# Sheet3.net
KiCad netlist of a schematic drawn in Altium Designer
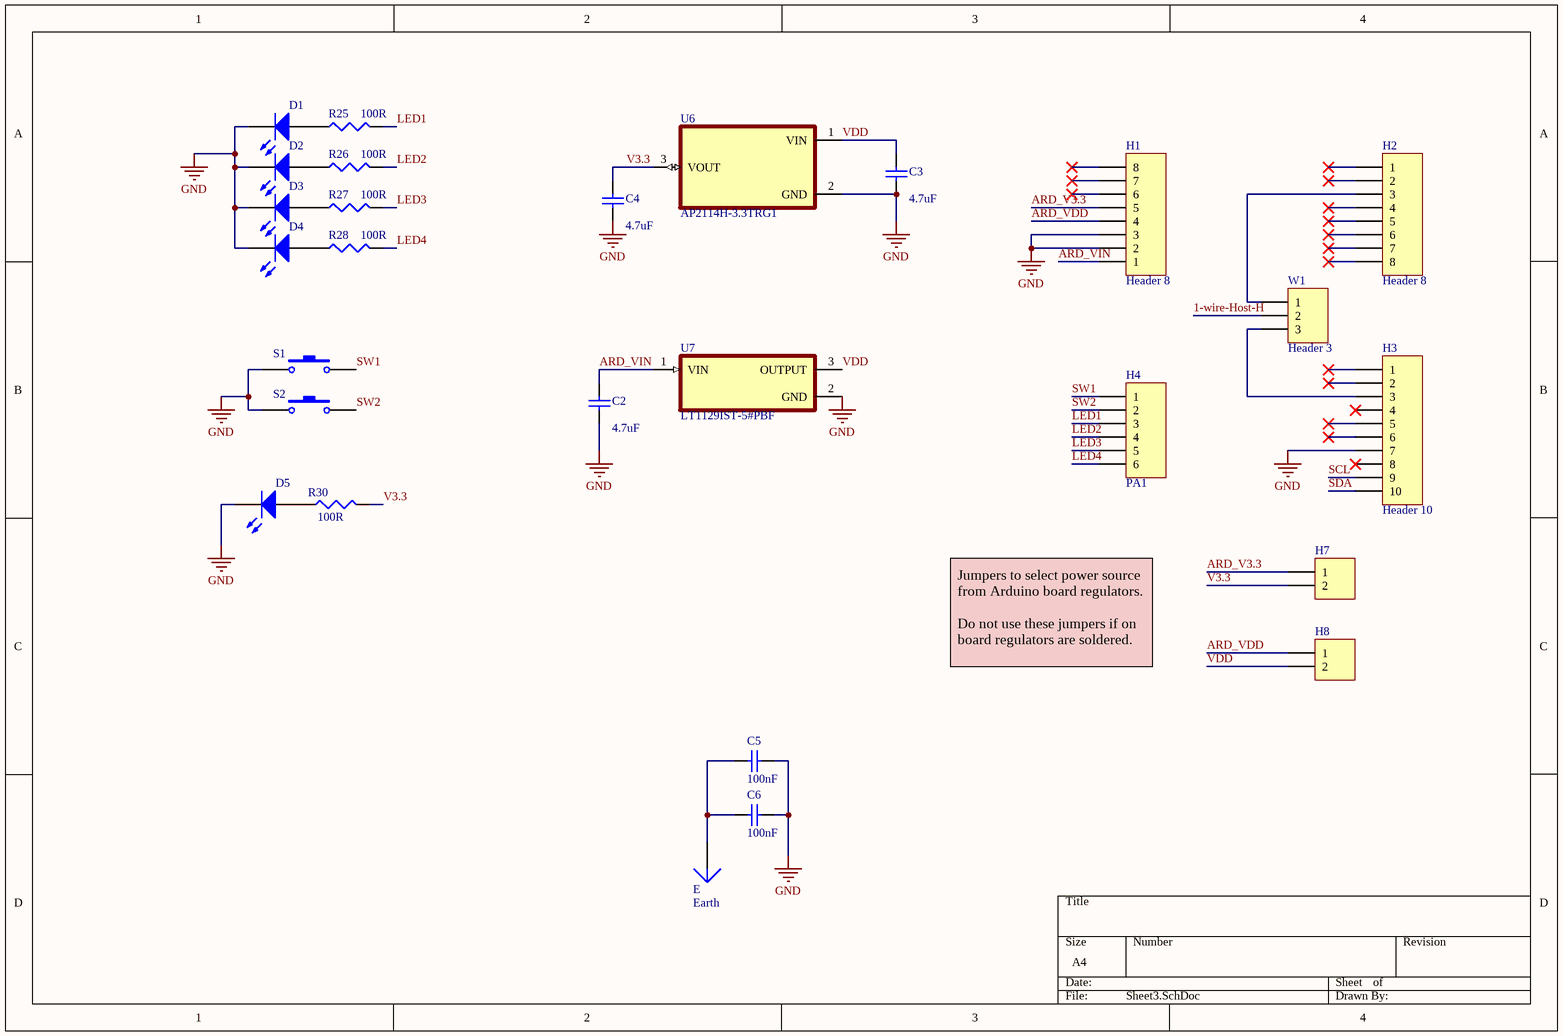
[diagram p0: Sheet3.SchDoc]

(export (version "E")
  (design (tool "Eeschema 10.0.6"))
  (components
    (comp (ref "C2")
      (value "4.7uF")
      (footprint "C0805")
      (description "Capacitor (Semiconductor SIM Model)")
      (fields (field (name "PUBLISHER") "Altium Limited"))
      (libsource (lib "Miscellaneous Devices") (part "Cap Semi"))
    )
    (comp (ref "C3")
      (value "4.7uF")
      (footprint "C0805")
      (description "Capacitor (Semiconductor SIM Model)")
      (fields (field (name "PUBLISHER") "Altium Limited"))
      (libsource (lib "Miscellaneous Devices") (part "Cap Semi"))
    )
    (comp (ref "C4")
      (value "4.7uF")
      (footprint "C0805")
      (description "Capacitor (Semiconductor SIM Model)")
      (fields (field (name "PUBLISHER") "Altium Limited"))
      (libsource (lib "Miscellaneous Devices") (part "Cap Semi"))
    )
    (comp (ref "C5")
      (value "100nF")
      (footprint "CAPC1608L")
      (description "Capacitor (Semiconductor SIM Model)")
      (fields (field (name "PUBLISHER") "Altium Limited"))
      (libsource (lib "Miscellaneous Devices") (part "Cap Semi"))
    )
    (comp (ref "C6")
      (value "100nF")
      (footprint "CAPC1608L")
      (description "Capacitor (Semiconductor SIM Model)")
      (fields (field (name "PUBLISHER") "Altium Limited"))
      (libsource (lib "Miscellaneous Devices") (part "Cap Semi"))
    )
    (comp (ref "D1")
      (value "~")
      (footprint "6-0805_N")
      (description "Typical BLUE SiC LED")
      (fields (field (name "PUBLISHER") "Altium Limited"))
      (libsource (lib "Miscellaneous Devices") (part "LED3"))
    )
    (comp (ref "D2")
      (value "~")
      (footprint "6-0805_N")
      (description "Typical BLUE SiC LED")
      (fields (field (name "PUBLISHER") "Altium Limited"))
      (libsource (lib "Miscellaneous Devices") (part "LED3"))
    )
    (comp (ref "D3")
      (value "~")
      (footprint "6-0805_N")
      (description "Typical BLUE SiC LED")
      (fields (field (name "PUBLISHER") "Altium Limited"))
      (libsource (lib "Miscellaneous Devices") (part "LED3"))
    )
    (comp (ref "D4")
      (value "~")
      (footprint "6-0805_N")
      (description "Typical BLUE SiC LED")
      (fields (field (name "PUBLISHER") "Altium Limited"))
      (libsource (lib "Miscellaneous Devices") (part "LED3"))
    )
    (comp (ref "D5")
      (value "~")
      (footprint "6-0805_N")
      (description "Typical BLUE SiC LED")
      (fields (field (name "PUBLISHER") "Altium Limited"))
      (libsource (lib "Miscellaneous Devices") (part "LED3"))
    )
    (comp (ref "E")
      (value "Earth")
      (footprint "PIN1")
      (description "Plug")
      (fields (field (name "PUBLISHER") "Altium Limited"))
      (libsource (lib "Miscellaneous Connectors") (part "Plug"))
    )
    (comp (ref "H1")
      (value "Header 8")
      (footprint "HDR1X8")
      (description "Header, 8-Pin")
      (fields (field (name "PUBLISHER") "Altium Limited"))
      (libsource (lib "") (part "Header 8_1"))
    )
    (comp (ref "H2")
      (value "Header 8")
      (footprint "HDR1X8")
      (description "Header, 8-Pin")
      (fields (field (name "PUBLISHER") "Altium Limited"))
      (libsource (lib "Miscellaneous Connectors") (part "Header 8"))
    )
    (comp (ref "H3")
      (value "Header 10")
      (footprint "HDR1X10")
      (description "Header, 10-Pin")
      (fields (field (name "PUBLISHER") "Altium Limited"))
      (libsource (lib "Miscellaneous Connectors") (part "Header 10"))
    )
    (comp (ref "H4")
      (value "PA1")
      (footprint "HDR1X6")
      (description "Header, 6-Pin")
      (fields (field (name "PUBLISHER") "Altium Limited"))
      (libsource (lib "Miscellaneous Connectors") (part "Header 6"))
    )
    (comp (ref "H7")
      (value "~")
      (footprint "HDR1X2")
      (description "Header, 2-Pin")
      (fields (field (name "PUBLISHER") "Altium Limited"))
      (libsource (lib "Miscellaneous Connectors") (part "Header 2"))
    )
    (comp (ref "H8")
      (value "~")
      (footprint "HDR1X2")
      (description "Header, 2-Pin")
      (fields (field (name "PUBLISHER") "Altium Limited"))
      (libsource (lib "Miscellaneous Connectors") (part "Header 2"))
    )
    (comp (ref "R25")
      (value "100R")
      (footprint "J1-0603")
      (description "Resistor")
      (fields (field (name "PUBLISHER") "Altium Limited"))
      (libsource (lib "Miscellaneous Devices") (part "Res3"))
    )
    (comp (ref "R26")
      (value "100R")
      (footprint "J1-0603")
      (description "Resistor")
      (fields (field (name "PUBLISHER") "Altium Limited"))
      (libsource (lib "Miscellaneous Devices") (part "Res3"))
    )
    (comp (ref "R27")
      (value "100R")
      (footprint "J1-0603")
      (description "Resistor")
      (fields (field (name "PUBLISHER") "Altium Limited"))
      (libsource (lib "Miscellaneous Devices") (part "Res3"))
    )
    (comp (ref "R28")
      (value "100R")
      (footprint "J1-0603")
      (description "Resistor")
      (fields (field (name "PUBLISHER") "Altium Limited"))
      (libsource (lib "Miscellaneous Devices") (part "Res3"))
    )
    (comp (ref "R30")
      (value "100R")
      (footprint "J1-0603")
      (description "Resistor")
      (fields (field (name "PUBLISHER") "Altium Limited"))
      (libsource (lib "Miscellaneous Devices") (part "Res3"))
    )
    (comp (ref "S1")
      (value "~")
      (footprint "PTS525SM08SMTR2LFS")
      (description "Switch")
      (fields (field (name "PUBLISHER") "Altium Limited"))
      (libsource (lib "Miscellaneous Devices") (part "SW-PB"))
    )
    (comp (ref "S2")
      (value "~")
      (footprint "PTS525SM08SMTR2LFS")
      (description "Switch")
      (fields (field (name "PUBLISHER") "Altium Limited"))
      (libsource (lib "Miscellaneous Devices") (part "SW-PB"))
    )
    (comp (ref "U6")
      (value "AP2114H-3.3TRG1")
      (footprint "AP2114H-3.3TRG1:SOT230P700X180-4N")
      (fields (field (name "MF") "{'manufacturer': u'Diodes Inc.'}"))
      (libsource (lib "*") (part "AP2114H-3.3TRG1"))
    )
    (comp (ref "U7")
      (value "LT1129IST-5#PBF")
      (footprint "LT1129IST-5#PBF:SOT230P700X180-4N")
      (fields (field (name "MF") "{'manufacturer': u'Analog Devices'}"))
      (libsource (lib "LT1129IST-5#PBF") (part "LT1129IST-5#PBF"))
    )
    (comp (ref "W1")
      (value "Header 3")
      (footprint "HDR1X3")
      (description "Header, 3-Pin")
      (fields (field (name "PUBLISHER") "Altium Limited"))
      (libsource (lib "Miscellaneous Connectors") (part "Header 3"))
    )
  )
  (nets
    (net (code "1") (name "/1-wire-Host-H") (class "Default")
      (node (ref "W1") (pin "2") (pinfunction "2_2") (pintype "passive"))
    )
    (net (code "2") (name "/ARD_V3.3") (class "Default")
      (node (ref "H1") (pin "5") (pinfunction "5_5") (pintype "passive"))
      (node (ref "H7") (pin "1") (pinfunction "1_1") (pintype "passive"))
    )
    (net (code "3") (name "/ARD_VDD") (class "Default")
      (node (ref "H1") (pin "4") (pinfunction "4_4") (pintype "passive"))
      (node (ref "H8") (pin "1") (pinfunction "1_1") (pintype "passive"))
    )
    (net (code "4") (name "/ARD_VIN") (class "Default")
      (node (ref "C2") (pin "2") (pinfunction "2_2") (pintype "passive"))
      (node (ref "H1") (pin "1") (pinfunction "1_1") (pintype "passive"))
      (node (ref "U7") (pin "1") (pinfunction "VIN_1") (pintype "input"))
    )
    (net (code "5") (name "/LED1") (class "Default")
      (node (ref "H4") (pin "3") (pinfunction "3_3") (pintype "passive"))
      (node (ref "R25") (pin "1") (pinfunction "1_1") (pintype "passive"))
    )
    (net (code "6") (name "/LED2") (class "Default")
      (node (ref "H4") (pin "4") (pinfunction "4_4") (pintype "passive"))
      (node (ref "R26") (pin "1") (pinfunction "1_1") (pintype "passive"))
    )
    (net (code "7") (name "/LED3") (class "Default")
      (node (ref "H4") (pin "5") (pinfunction "5_5") (pintype "passive"))
      (node (ref "R27") (pin "1") (pinfunction "1_1") (pintype "passive"))
    )
    (net (code "8") (name "/LED4") (class "Default")
      (node (ref "H4") (pin "6") (pinfunction "6_6") (pintype "passive"))
      (node (ref "R28") (pin "1") (pinfunction "1_1") (pintype "passive"))
    )
    (net (code "9") (name "/SCL") (class "Default")
      (node (ref "H3") (pin "9") (pinfunction "9_9") (pintype "passive"))
    )
    (net (code "10") (name "/SDA") (class "Default")
      (node (ref "H3") (pin "10") (pinfunction "10_10") (pintype "passive"))
    )
    (net (code "11") (name "/SW1") (class "Default")
      (node (ref "H4") (pin "1") (pinfunction "1_1") (pintype "passive"))
      (node (ref "S1") (pin "2") (pinfunction "2_2") (pintype "passive"))
    )
    (net (code "12") (name "/SW2") (class "Default")
      (node (ref "H4") (pin "2") (pinfunction "2_2") (pintype "passive"))
      (node (ref "S2") (pin "2") (pinfunction "2_2") (pintype "passive"))
    )
    (net (code "13") (name "/V3.3") (class "Default")
      (node (ref "C4") (pin "2") (pinfunction "2_2") (pintype "passive"))
      (node (ref "H7") (pin "2") (pinfunction "2_2") (pintype "passive"))
      (node (ref "R30") (pin "1") (pinfunction "1_1") (pintype "passive"))
      (node (ref "U6") (pin "3") (pinfunction "VOUT_3") (pintype "bidirectional"))
    )
    (net (code "14") (name "/VDD") (class "Default")
      (node (ref "C3") (pin "2") (pinfunction "2_2") (pintype "passive"))
      (node (ref "H8") (pin "2") (pinfunction "2_2") (pintype "passive"))
      (node (ref "U6") (pin "1") (pinfunction "VIN_1") (pintype "power_in"))
      (node (ref "U7") (pin "3") (pinfunction "OUTPUT_3") (pintype "power_in"))
    )
    (net (code "15") (name "GND") (class "Default")
      (node (ref "C2") (pin "1") (pinfunction "1_1") (pintype "passive"))
      (node (ref "C3") (pin "1") (pinfunction "1_1") (pintype "passive"))
      (node (ref "C4") (pin "1") (pinfunction "1_1") (pintype "passive"))
      (node (ref "C5") (pin "2") (pinfunction "2_2") (pintype "passive"))
      (node (ref "C6") (pin "2") (pinfunction "2_2") (pintype "passive"))
      (node (ref "D1") (pin "2") (pinfunction "K_2") (pintype "passive"))
      (node (ref "D2") (pin "2") (pinfunction "K_2") (pintype "passive"))
      (node (ref "D3") (pin "2") (pinfunction "K_2") (pintype "passive"))
      (node (ref "D4") (pin "2") (pinfunction "K_2") (pintype "passive"))
      (node (ref "D5") (pin "2") (pinfunction "K_2") (pintype "passive"))
      (node (ref "H1") (pin "2") (pinfunction "2_2") (pintype "passive"))
      (node (ref "H1") (pin "3") (pinfunction "3_3") (pintype "passive"))
      (node (ref "H3") (pin "7") (pinfunction "7_7") (pintype "passive"))
      (node (ref "S1") (pin "1") (pinfunction "1_1") (pintype "passive"))
      (node (ref "S2") (pin "1") (pinfunction "1_1") (pintype "passive"))
      (node (ref "U6") (pin "2") (pinfunction "GND_2") (pintype "power_in"))
      (node (ref "U7") (pin "2") (pinfunction "GND_2") (pintype "power_in"))
    )
    (net (code "16") (name "Net-(C5-Pad1)") (class "Default")
      (node (ref "C5") (pin "1") (pinfunction "1_1") (pintype "passive"))
      (node (ref "C6") (pin "1") (pinfunction "1_1") (pintype "passive"))
      (node (ref "E") (pin "1") (pinfunction "1_1") (pintype "passive"))
    )
    (net (code "17") (name "Net-(D1-A)") (class "Default")
      (node (ref "D1") (pin "1") (pinfunction "A_1") (pintype "passive"))
      (node (ref "R25") (pin "2") (pinfunction "2_2") (pintype "passive"))
    )
    (net (code "18") (name "Net-(D2-A)") (class "Default")
      (node (ref "D2") (pin "1") (pinfunction "A_1") (pintype "passive"))
      (node (ref "R26") (pin "2") (pinfunction "2_2") (pintype "passive"))
    )
    (net (code "19") (name "Net-(D3-A)") (class "Default")
      (node (ref "D3") (pin "1") (pinfunction "A_1") (pintype "passive"))
      (node (ref "R27") (pin "2") (pinfunction "2_2") (pintype "passive"))
    )
    (net (code "20") (name "Net-(D4-A)") (class "Default")
      (node (ref "D4") (pin "1") (pinfunction "A_1") (pintype "passive"))
      (node (ref "R28") (pin "2") (pinfunction "2_2") (pintype "passive"))
    )
    (net (code "21") (name "Net-(D5-A)") (class "Default")
      (node (ref "D5") (pin "1") (pinfunction "A_1") (pintype "passive"))
      (node (ref "R30") (pin "2") (pinfunction "2_2") (pintype "passive"))
    )
    (net (code "22") (name "Net-(H2-Pad3)") (class "Default")
      (node (ref "H2") (pin "3") (pinfunction "3_3") (pintype "passive"))
      (node (ref "W1") (pin "1") (pinfunction "1_1") (pintype "passive"))
    )
    (net (code "23") (name "Net-(H3-Pad3)") (class "Default")
      (node (ref "H3") (pin "3") (pinfunction "3_3") (pintype "passive"))
      (node (ref "W1") (pin "3") (pinfunction "3_3") (pintype "passive"))
    )
    (net (code "24") (name "unconnected-(H1-Pad6)") (class "Default")
      (node (ref "H1") (pin "6") (pinfunction "6_6") (pintype "passive+no_connect"))
    )
    (net (code "25") (name "unconnected-(H1-Pad7)") (class "Default")
      (node (ref "H1") (pin "7") (pinfunction "7_7") (pintype "passive+no_connect"))
    )
    (net (code "26") (name "unconnected-(H1-Pad8)") (class "Default")
      (node (ref "H1") (pin "8") (pinfunction "8_8") (pintype "passive+no_connect"))
    )
    (net (code "27") (name "unconnected-(H2-Pad1)") (class "Default")
      (node (ref "H2") (pin "1") (pinfunction "1_1") (pintype "passive+no_connect"))
    )
    (net (code "28") (name "unconnected-(H2-Pad2)") (class "Default")
      (node (ref "H2") (pin "2") (pinfunction "2_2") (pintype "passive+no_connect"))
    )
    (net (code "29") (name "unconnected-(H2-Pad4)") (class "Default")
      (node (ref "H2") (pin "4") (pinfunction "4_4") (pintype "passive+no_connect"))
    )
    (net (code "30") (name "unconnected-(H2-Pad5)") (class "Default")
      (node (ref "H2") (pin "5") (pinfunction "5_5") (pintype "passive+no_connect"))
    )
    (net (code "31") (name "unconnected-(H2-Pad6)") (class "Default")
      (node (ref "H2") (pin "6") (pinfunction "6_6") (pintype "passive+no_connect"))
    )
    (net (code "32") (name "unconnected-(H2-Pad7)") (class "Default")
      (node (ref "H2") (pin "7") (pinfunction "7_7") (pintype "passive+no_connect"))
    )
    (net (code "33") (name "unconnected-(H2-Pad8)") (class "Default")
      (node (ref "H2") (pin "8") (pinfunction "8_8") (pintype "passive+no_connect"))
    )
    (net (code "34") (name "unconnected-(H3-Pad1)") (class "Default")
      (node (ref "H3") (pin "1") (pinfunction "1_1") (pintype "passive+no_connect"))
    )
    (net (code "35") (name "unconnected-(H3-Pad2)") (class "Default")
      (node (ref "H3") (pin "2") (pinfunction "2_2") (pintype "passive+no_connect"))
    )
    (net (code "36") (name "unconnected-(H3-Pad4)") (class "Default")
      (node (ref "H3") (pin "4") (pinfunction "4_4") (pintype "passive+no_connect"))
    )
    (net (code "37") (name "unconnected-(H3-Pad5)") (class "Default")
      (node (ref "H3") (pin "5") (pinfunction "5_5") (pintype "passive+no_connect"))
    )
    (net (code "38") (name "unconnected-(H3-Pad6)") (class "Default")
      (node (ref "H3") (pin "6") (pinfunction "6_6") (pintype "passive+no_connect"))
    )
    (net (code "39") (name "unconnected-(H3-Pad8)") (class "Default")
      (node (ref "H3") (pin "8") (pinfunction "8_8") (pintype "passive+no_connect"))
    )
  )
)
